# CW340_SAM3X_MISC.net
KiCad netlist of a schematic drawn in Altium Designer
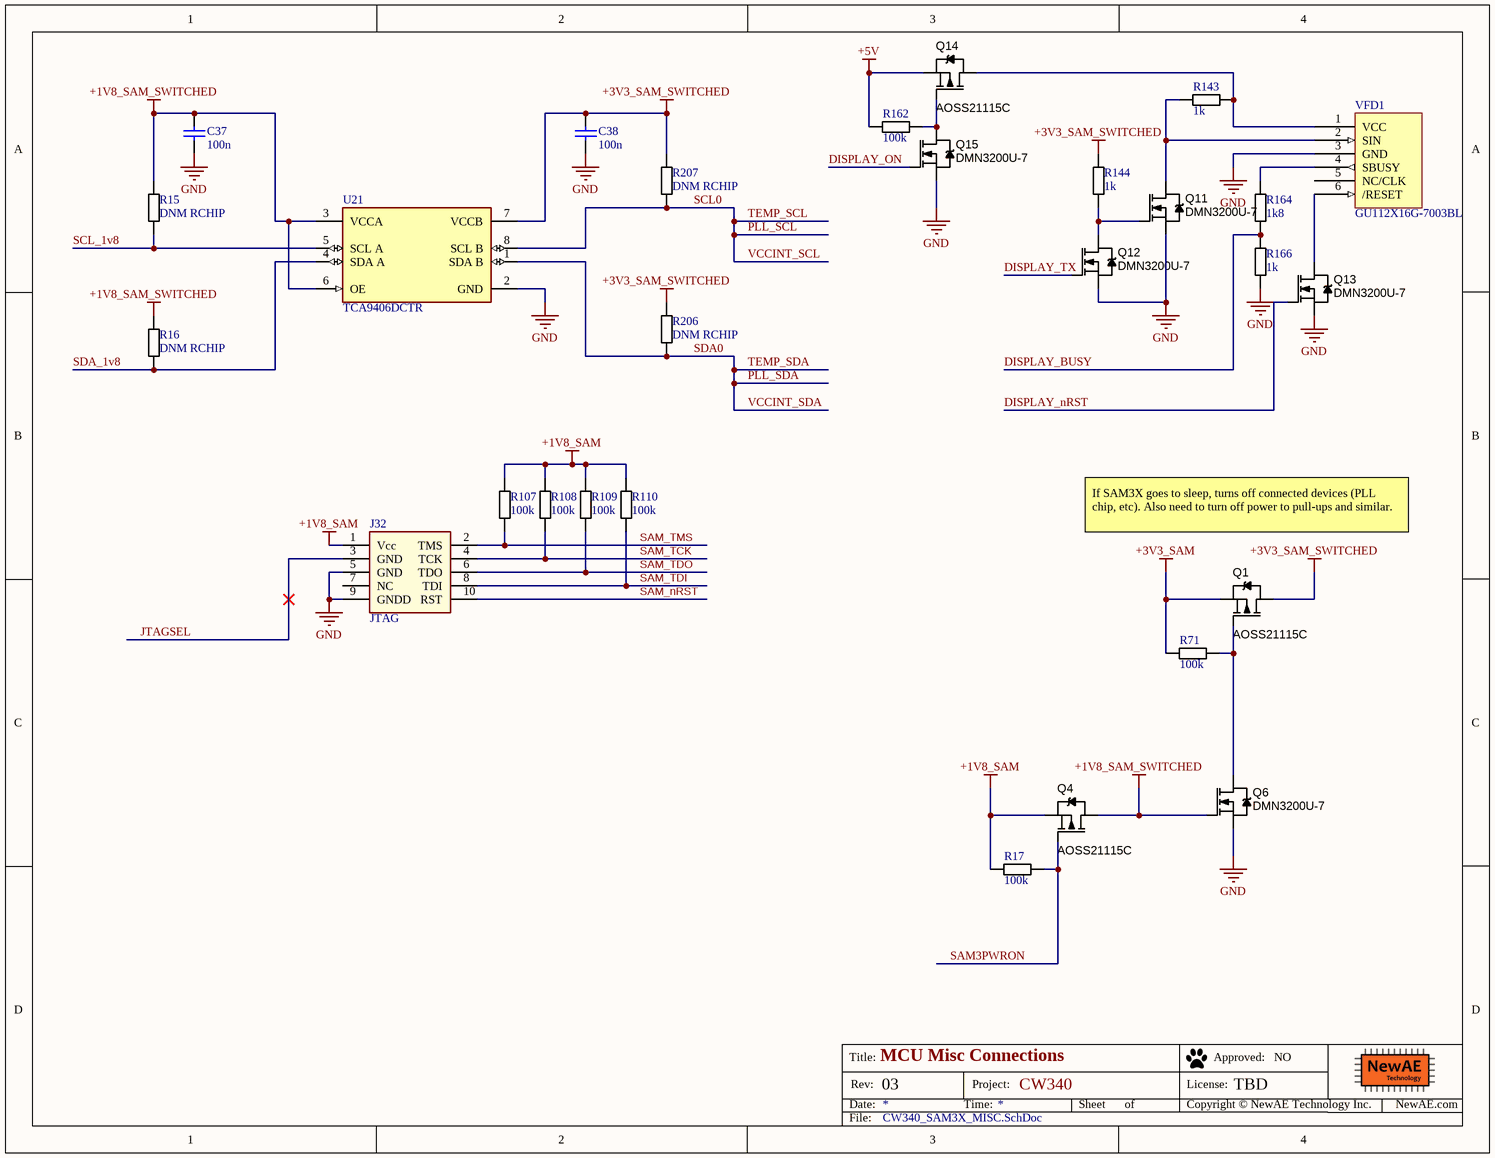
[diagram p0: CW340_SAM3X_MISC.SchDoc]

(export (version "E")
  (design (tool "Eeschema 10.0.6"))
  (components
    (comp (ref "C37")
      (value "100n")
      (footprint "CAPC0402_M")
      (description "100n, 0402")
      (fields (field (name "PART NUMBER") "CCHIP-100n-0402"))
      (libsource (lib "NewAE_AltiumLib") (part "CAP"))
    )
    (comp (ref "C38")
      (value "100n")
      (footprint "CAPC0402_M")
      (description "100n, 0402")
      (fields (field (name "PART NUMBER") "CCHIP-100n-0402"))
      (libsource (lib "NewAE_AltiumLib") (part "CAP"))
    )
    (comp (ref "J32")
      (value "JTAG")
      (footprint "0.5mm_SMD_Header_5x2")
      (description "10 Pin Cortex Program & Debug 0.5mm pitch")
      (fields (field (name "PART NUMBER") "Cortex_Debug_Header_10Pin"))
      (libsource (lib "CW550") (part "Cortex_Debug_Header_10Pin"))
    )
    (comp (ref "Q1")
      (value "AOSS21115C")
      (footprint "SOT95P245X110-3M")
      (description "P-Channel, 4.5A, 1.8V Logic Level")
      (libsource (lib "NewAE_AltiumLib") (part "MOSFET_P_GSD"))
    )
    (comp (ref "Q4")
      (value "AOSS21115C")
      (footprint "SOT95P245X110-3M")
      (description "P-Channel, 4.5A, 1.8V Logic Level")
      (libsource (lib "NewAE_AltiumLib") (part "MOSFET_P_GSD"))
    )
    (comp (ref "Q6")
      (value "DMN3200U-7")
      (footprint "SOT95P245X110-3M")
      (description "MOSFET N-CH 30V 2.2A SOT23-3")
      (libsource (lib "NewAE_AltiumLib") (part "MOSFET_N_GSD"))
    )
    (comp (ref "Q11")
      (value "DMN3200U-7")
      (footprint "SOT95P245X110-3M")
      (description "MOSFET N-CH 30V 2.2A SOT23-3")
      (libsource (lib "NewAE_AltiumLib") (part "MOSFET_N_GSD"))
    )
    (comp (ref "Q12")
      (value "DMN3200U-7")
      (footprint "SOT95P245X110-3M")
      (description "MOSFET N-CH 30V 2.2A SOT23-3")
      (libsource (lib "NewAE_AltiumLib") (part "MOSFET_N_GSD"))
    )
    (comp (ref "Q13")
      (value "DMN3200U-7")
      (footprint "SOT95P245X110-3M")
      (description "MOSFET N-CH 30V 2.2A SOT23-3")
      (libsource (lib "NewAE_AltiumLib") (part "MOSFET_N_GSD"))
    )
    (comp (ref "Q14")
      (value "AOSS21115C")
      (footprint "SOT95P245X110-3M")
      (description "P-Channel, 4.5A, 1.8V Logic Level")
      (libsource (lib "NewAE_AltiumLib") (part "MOSFET_P_GSD"))
    )
    (comp (ref "Q15")
      (value "DMN3200U-7")
      (footprint "SOT95P245X110-3M")
      (description "MOSFET N-CH 30V 2.2A SOT23-3")
      (libsource (lib "NewAE_AltiumLib") (part "MOSFET_N_GSD"))
    )
    (comp (ref "R15")
      (value "DNM RCHIP")
      (footprint "RESC1608X55N")
      (description "Do Not Mount Resistor")
      (fields (field (name "PART NUMBER") "RCHIP-DNM-0603"))
      (libsource (lib "NewAE_AltiumLib") (part "RES-EU"))
    )
    (comp (ref "R16")
      (value "DNM RCHIP")
      (footprint "RESC1608X55N")
      (description "Do Not Mount Resistor")
      (fields (field (name "PART NUMBER") "RCHIP-DNM-0603"))
      (libsource (lib "NewAE_AltiumLib") (part "RES-EU"))
    )
    (comp (ref "R17")
      (value "100k")
      (footprint "RESC1608X55N")
      (description "100k res, 0603, 1%, 1/10W")
      (fields (field (name "PART NUMBER") "RCHIP-100K-0603") (field (name "TOLERANCE") "1%"))
      (libsource (lib "") (part "RES-EU_1"))
    )
    (comp (ref "R71")
      (value "100k")
      (footprint "RESC1608X55N")
      (description "100k res, 0603, 1%, 1/10W")
      (fields (field (name "PART NUMBER") "RCHIP-100K-0603") (field (name "TOLERANCE") "1%"))
      (libsource (lib "") (part "RES-EU_1"))
    )
    (comp (ref "R107")
      (value "100k")
      (footprint "RESC1005X40N")
      (description "100k res, 0402, 1%, 1/16W")
      (fields (field (name "PART NUMBER") "RCHIP-100K-0402") (field (name "TOLERANCE") "1%"))
      (libsource (lib "NewAE_AltiumLib") (part "RES-EU"))
    )
    (comp (ref "R108")
      (value "100k")
      (footprint "RESC1005X40N")
      (description "100k res, 0402, 1%, 1/16W")
      (fields (field (name "PART NUMBER") "RCHIP-100K-0402") (field (name "TOLERANCE") "1%"))
      (libsource (lib "NewAE_AltiumLib") (part "RES-EU"))
    )
    (comp (ref "R109")
      (value "100k")
      (footprint "RESC1005X40N")
      (description "100k res, 0402, 1%, 1/16W")
      (fields (field (name "PART NUMBER") "RCHIP-100K-0402") (field (name "TOLERANCE") "1%"))
      (libsource (lib "NewAE_AltiumLib") (part "RES-EU"))
    )
    (comp (ref "R110")
      (value "100k")
      (footprint "RESC1005X40N")
      (description "100k res, 0402, 1%, 1/16W")
      (fields (field (name "PART NUMBER") "RCHIP-100K-0402") (field (name "TOLERANCE") "1%"))
      (libsource (lib "NewAE_AltiumLib") (part "RES-EU"))
    )
    (comp (ref "R143")
      (value "1k")
      (footprint "RESC1005X40N")
      (description "1k res, 0402, 1%, 1/16W")
      (fields (field (name "PART NUMBER") "RCHIP-1K-0402") (field (name "TOLERANCE") "1%"))
      (libsource (lib "") (part "RES-EU_1"))
    )
    (comp (ref "R144")
      (value "1k")
      (footprint "RESC1005X40N")
      (description "1k res, 0402, 1%, 1/16W")
      (fields (field (name "PART NUMBER") "RCHIP-1K-0402") (field (name "TOLERANCE") "1%"))
      (libsource (lib "NewAE_AltiumLib") (part "RES-EU"))
    )
    (comp (ref "R162")
      (value "100k")
      (footprint "RESC1608X55N")
      (description "100k res, 0603, 1%, 1/10W")
      (fields (field (name "PART NUMBER") "RCHIP-100K-0603") (field (name "TOLERANCE") "1%"))
      (libsource (lib "") (part "RES-EU_1"))
    )
    (comp (ref "R164")
      (value "1k8")
      (footprint "RESC1005X40N")
      (description "1k8 res, 0402, 1%, 1/16W")
      (fields (field (name "PART NUMBER") "RCHIP-1K8-0402") (field (name "TOLERANCE") "1%"))
      (libsource (lib "NewAE_AltiumLib") (part "RES-EU"))
    )
    (comp (ref "R166")
      (value "1k")
      (footprint "RESC1005X40N")
      (description "1k res, 0402, 1%, 1/16W")
      (fields (field (name "PART NUMBER") "RCHIP-1K-0402") (field (name "TOLERANCE") "1%"))
      (libsource (lib "NewAE_AltiumLib") (part "RES-EU"))
    )
    (comp (ref "R206")
      (value "DNM RCHIP")
      (footprint "RESC1608X55N")
      (description "Do Not Mount Resistor")
      (fields (field (name "PART NUMBER") "RCHIP-DNM-0603"))
      (libsource (lib "NewAE_AltiumLib") (part "RES-EU"))
    )
    (comp (ref "R207")
      (value "DNM RCHIP")
      (footprint "RESC1608X55N")
      (description "Do Not Mount Resistor")
      (fields (field (name "PART NUMBER") "RCHIP-DNM-0603"))
      (libsource (lib "NewAE_AltiumLib") (part "RES-EU"))
    )
    (comp (ref "U21")
      (value "TCA9406DCTR")
      (footprint "FP-DCT0008A-MFG")
      (description "IC TRNSLTR BIDIRECTIONAL SM8")
      (libsource (lib "Altium Content Vault") (part "3f41b918c53748b0080b1005cc648b3"))
    )
    (comp (ref "VFD1")
      (value "GU112X16G-7003BL")
      (footprint "GU112X16G-7003BL")
      (description "VFD Display")
      (libsource (lib "NewAE_AltiumLib") (part "GU112X16G-7003BL"))
    )
  )
  (nets
    (net (code "1") (name "+1V8_SAM") (class "Default")
      (node (ref "J32") (pin "1") (pinfunction "Vcc_1") (pintype "passive"))
      (node (ref "Q4") (pin "2") (pinfunction "S_2") (pintype "passive"))
      (node (ref "R107") (pin "1") (pinfunction "1_1") (pintype "passive"))
      (node (ref "R108") (pin "1") (pinfunction "1_1") (pintype "passive"))
      (node (ref "R109") (pin "1") (pinfunction "1_1") (pintype "passive"))
      (node (ref "R110") (pin "1") (pinfunction "1_1") (pintype "passive"))
      (node (ref "R17") (pin "1") (pinfunction "1_1") (pintype "passive"))
    )
    (net (code "2") (name "+1V8_SAM_SWITCHED") (class "Default")
      (node (ref "C37") (pin "1") (pinfunction "1_1") (pintype "passive"))
      (node (ref "Q4") (pin "3") (pinfunction "D_3") (pintype "passive"))
      (node (ref "Q6") (pin "1") (pinfunction "G_1") (pintype "passive"))
      (node (ref "R15") (pin "1") (pinfunction "1_1") (pintype "passive"))
      (node (ref "R16") (pin "1") (pinfunction "1_1") (pintype "passive"))
      (node (ref "U21") (pin "3") (pinfunction "VCCA_3") (pintype "power_in"))
      (node (ref "U21") (pin "6") (pinfunction "OE_6") (pintype "input"))
    )
    (net (code "3") (name "+3V3_SAM") (class "Default")
      (node (ref "Q1") (pin "2") (pinfunction "S_2") (pintype "passive"))
      (node (ref "R71") (pin "1") (pinfunction "1_1") (pintype "passive"))
    )
    (net (code "4") (name "+3V3_SAM_SWITCHED") (class "Default")
      (node (ref "C38") (pin "1") (pinfunction "1_1") (pintype "passive"))
      (node (ref "Q1") (pin "3") (pinfunction "D_3") (pintype "passive"))
      (node (ref "R144") (pin "1") (pinfunction "1_1") (pintype "passive"))
      (node (ref "R206") (pin "1") (pinfunction "1_1") (pintype "passive"))
      (node (ref "R207") (pin "1") (pinfunction "1_1") (pintype "passive"))
      (node (ref "U21") (pin "7") (pinfunction "VCCB_7") (pintype "power_in"))
    )
    (net (code "5") (name "+5V") (class "Default")
      (node (ref "Q14") (pin "2") (pinfunction "S_2") (pintype "passive"))
      (node (ref "R162") (pin "1") (pinfunction "1_1") (pintype "passive"))
    )
    (net (code "6") (name "/DISPLAY_BUSY") (class "Default")
      (node (ref "R164") (pin "2") (pinfunction "2_2") (pintype "passive"))
      (node (ref "R166") (pin "1") (pinfunction "1_1") (pintype "passive"))
    )
    (net (code "7") (name "/DISPLAY_ON") (class "Default")
      (node (ref "Q15") (pin "1") (pinfunction "G_1") (pintype "passive"))
    )
    (net (code "8") (name "/DISPLAY_TX") (class "Default")
      (node (ref "Q12") (pin "1") (pinfunction "G_1") (pintype "passive"))
    )
    (net (code "9") (name "/DISPLAY_nRST") (class "Default")
      (node (ref "Q13") (pin "1") (pinfunction "G_1") (pintype "passive"))
    )
    (net (code "10") (name "/JTAGSEL") (class "Default")
      (node (ref "J32") (pin "3") (pinfunction "GND_3") (pintype "passive"))
    )
    (net (code "11") (name "/PLL_SCL") (class "Default")
      (node (ref "R207") (pin "2") (pinfunction "2_2") (pintype "passive"))
      (node (ref "U21") (pin "8") (pinfunction "SCL_B_8") (pintype "bidirectional"))
    )
    (net (code "12") (name "/PLL_SDA") (class "Default")
      (node (ref "R206") (pin "2") (pinfunction "2_2") (pintype "passive"))
      (node (ref "U21") (pin "1") (pinfunction "SDA_B_1") (pintype "bidirectional"))
    )
    (net (code "13") (name "/SAM3PWRON") (class "Default")
      (node (ref "Q4") (pin "1") (pinfunction "G_1") (pintype "passive"))
      (node (ref "R17") (pin "2") (pinfunction "2_2") (pintype "passive"))
    )
    (net (code "14") (name "/SAM_TCK") (class "Default")
      (node (ref "J32") (pin "4") (pinfunction "TCK_4") (pintype "passive"))
      (node (ref "R108") (pin "2") (pinfunction "2_2") (pintype "passive"))
    )
    (net (code "15") (name "/SAM_TDI") (class "Default")
      (node (ref "J32") (pin "8") (pinfunction "TDI_8") (pintype "passive"))
      (node (ref "R110") (pin "2") (pinfunction "2_2") (pintype "passive"))
    )
    (net (code "16") (name "/SAM_TDO") (class "Default")
      (node (ref "J32") (pin "6") (pinfunction "TDO_6") (pintype "passive"))
      (node (ref "R109") (pin "2") (pinfunction "2_2") (pintype "passive"))
    )
    (net (code "17") (name "/SAM_TMS") (class "Default")
      (node (ref "J32") (pin "2") (pinfunction "TMS_2") (pintype "passive"))
      (node (ref "R107") (pin "2") (pinfunction "2_2") (pintype "passive"))
    )
    (net (code "18") (name "/SAM_nRST") (class "Default")
      (node (ref "J32") (pin "10") (pinfunction "RST_10") (pintype "passive"))
    )
    (net (code "19") (name "/SCL_1v8") (class "Default")
      (node (ref "R15") (pin "2") (pinfunction "2_2") (pintype "passive"))
      (node (ref "U21") (pin "5") (pinfunction "SCL_A_5") (pintype "bidirectional"))
    )
    (net (code "20") (name "/SDA_1v8") (class "Default")
      (node (ref "R16") (pin "2") (pinfunction "2_2") (pintype "passive"))
      (node (ref "U21") (pin "4") (pinfunction "SDA_A_4") (pintype "bidirectional"))
    )
    (net (code "21") (name "GND") (class "Default")
      (node (ref "C37") (pin "2") (pinfunction "2_2") (pintype "passive"))
      (node (ref "C38") (pin "2") (pinfunction "2_2") (pintype "passive"))
      (node (ref "J32") (pin "5") (pinfunction "GND_5") (pintype "passive"))
      (node (ref "J32") (pin "9") (pinfunction "GNDD_9") (pintype "passive"))
      (node (ref "Q11") (pin "2") (pinfunction "S_2") (pintype "passive"))
      (node (ref "Q12") (pin "2") (pinfunction "S_2") (pintype "passive"))
      (node (ref "Q13") (pin "2") (pinfunction "S_2") (pintype "passive"))
      (node (ref "Q15") (pin "2") (pinfunction "S_2") (pintype "passive"))
      (node (ref "Q6") (pin "2") (pinfunction "S_2") (pintype "passive"))
      (node (ref "R166") (pin "2") (pinfunction "2_2") (pintype "passive"))
      (node (ref "U21") (pin "2") (pinfunction "GND_2") (pintype "power_in"))
      (node (ref "VFD1") (pin "3") (pinfunction "GND_3") (pintype "power_in"))
    )
    (net (code "22") (name "Net-(Q1-G)") (class "Default")
      (node (ref "Q1") (pin "1") (pinfunction "G_1") (pintype "passive"))
      (node (ref "Q6") (pin "3") (pinfunction "D_3") (pintype "passive"))
      (node (ref "R71") (pin "2") (pinfunction "2_2") (pintype "passive"))
    )
    (net (code "23") (name "Net-(Q11-D)") (class "Default")
      (node (ref "Q11") (pin "3") (pinfunction "D_3") (pintype "passive"))
      (node (ref "R143") (pin "1") (pinfunction "1_1") (pintype "passive"))
      (node (ref "VFD1") (pin "2") (pinfunction "SIN_2") (pintype "input"))
    )
    (net (code "24") (name "Net-(Q11-G)") (class "Default")
      (node (ref "Q11") (pin "1") (pinfunction "G_1") (pintype "passive"))
      (node (ref "Q12") (pin "3") (pinfunction "D_3") (pintype "passive"))
      (node (ref "R144") (pin "2") (pinfunction "2_2") (pintype "passive"))
    )
    (net (code "25") (name "Net-(Q13-D)") (class "Default")
      (node (ref "Q13") (pin "3") (pinfunction "D_3") (pintype "passive"))
      (node (ref "VFD1") (pin "6") (pinfunction "/RESET_6") (pintype "input"))
    )
    (net (code "26") (name "Net-(Q14-D)") (class "Default")
      (node (ref "Q14") (pin "3") (pinfunction "D_3") (pintype "passive"))
      (node (ref "R143") (pin "2") (pinfunction "2_2") (pintype "passive"))
      (node (ref "VFD1") (pin "1") (pinfunction "VCC_1") (pintype "power_in"))
    )
    (net (code "27") (name "Net-(Q14-G)") (class "Default")
      (node (ref "Q14") (pin "1") (pinfunction "G_1") (pintype "passive"))
      (node (ref "Q15") (pin "3") (pinfunction "D_3") (pintype "passive"))
      (node (ref "R162") (pin "2") (pinfunction "2_2") (pintype "passive"))
    )
    (net (code "28") (name "Net-(VFD1-SBUSY)") (class "Default")
      (node (ref "R164") (pin "1") (pinfunction "1_1") (pintype "passive"))
      (node (ref "VFD1") (pin "4") (pinfunction "SBUSY_4") (pintype "output"))
    )
    (net (code "29") (name "unconnected-(J32-NC-Pad7)") (class "Default")
      (node (ref "J32") (pin "7") (pinfunction "NC_7") (pintype "passive"))
    )
    (net (code "30") (name "unconnected-(VFD1-NC{slash}CLK-Pad5)") (class "Default")
      (node (ref "VFD1") (pin "5") (pinfunction "NC/CLK_5") (pintype "passive"))
    )
  )
)
